# TMC2160.net
KiCad netlist of a schematic drawn in Altium Designer
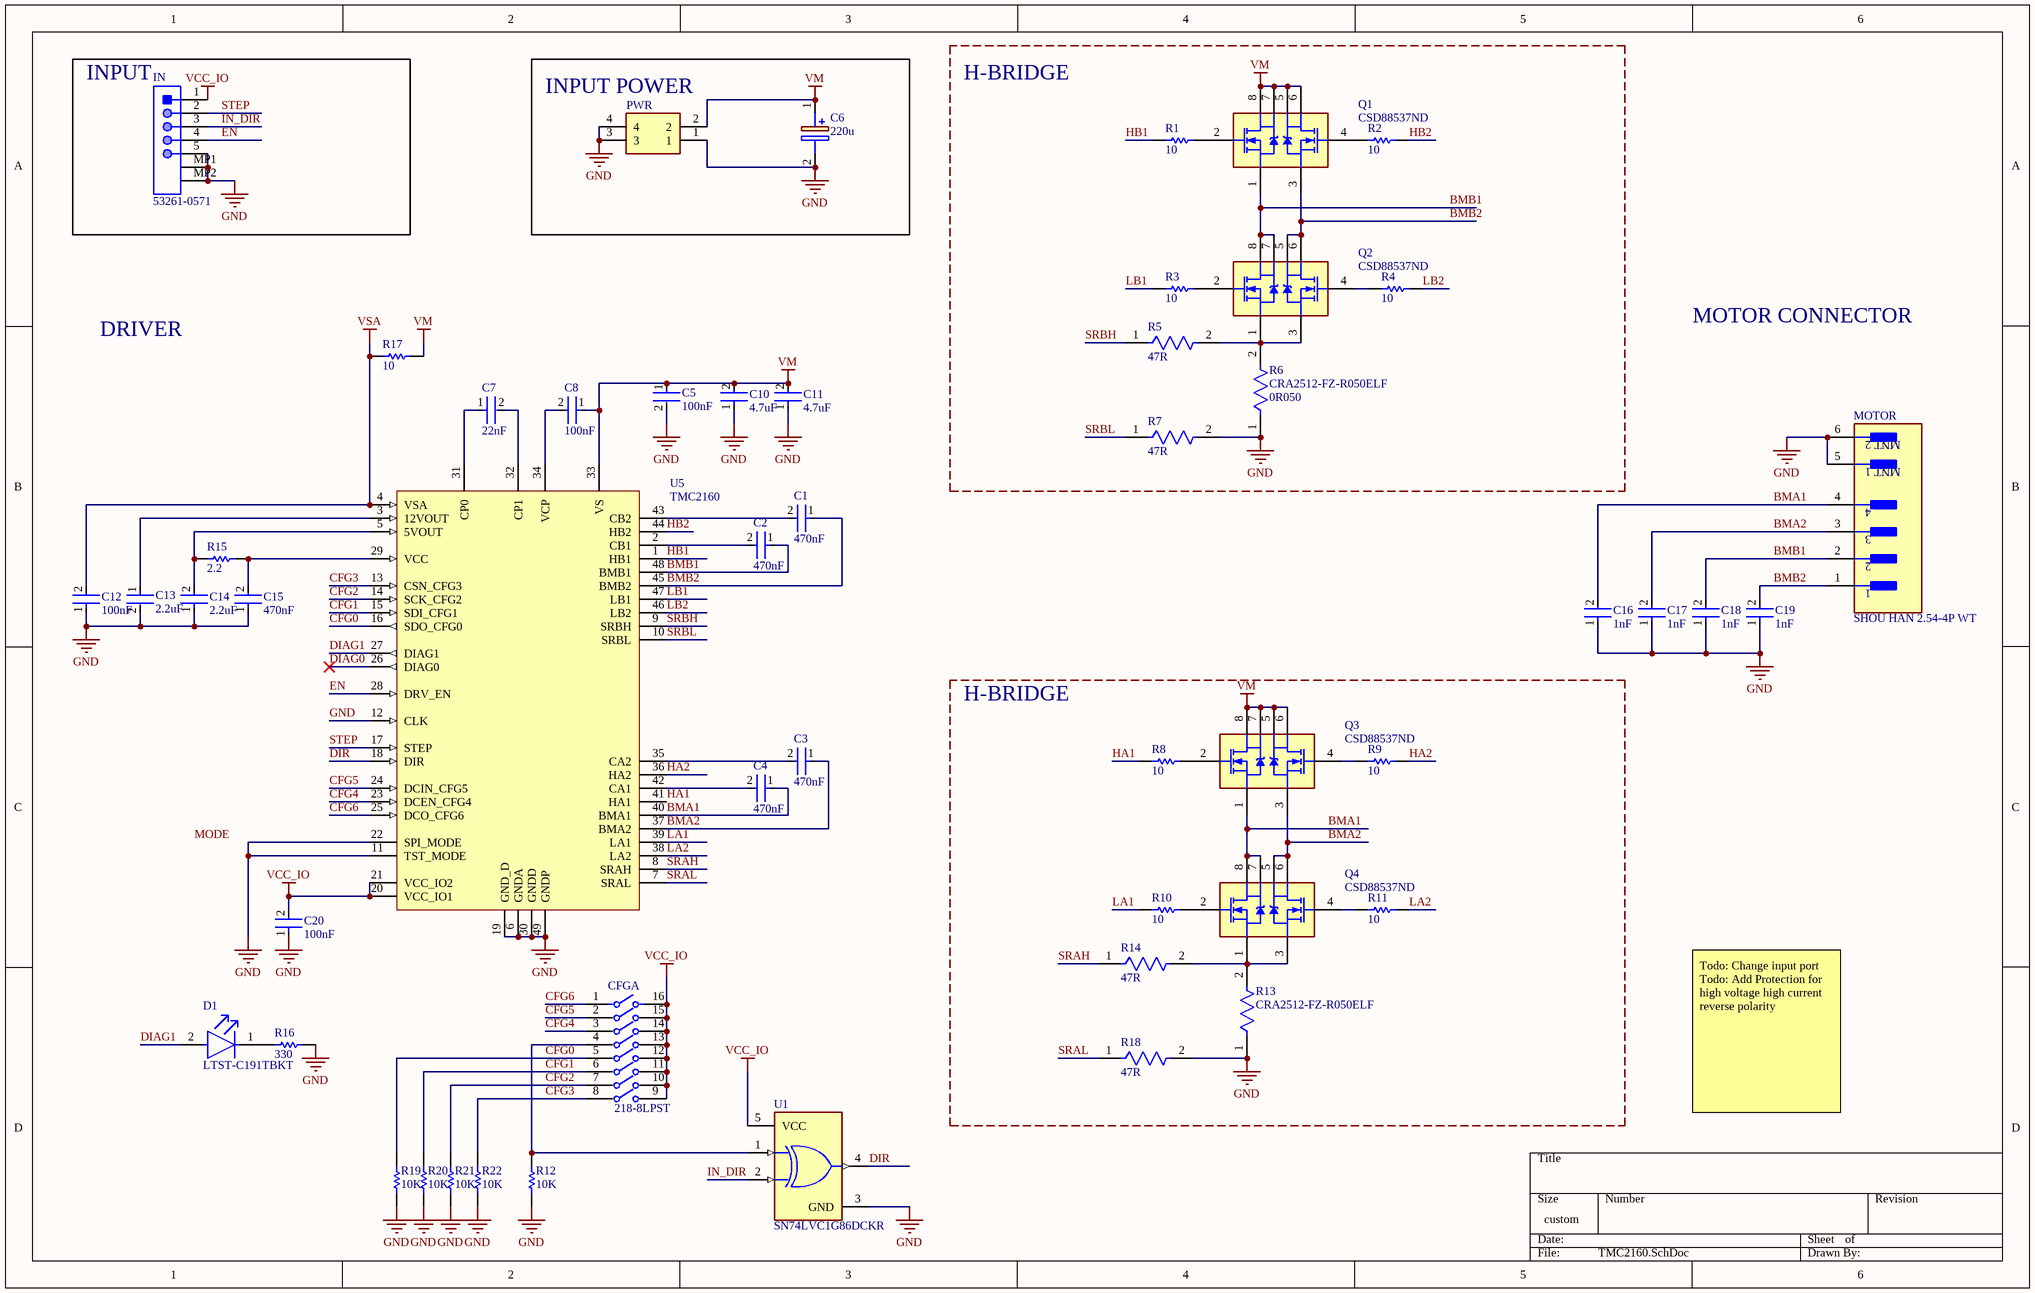
[diagram p0: TMC2160.SchDoc]

(export (version "E")
  (design (tool "Eeschema 10.0.6"))
  (components
    (comp (ref "C1")
      (value "470nF")
      (footprint "FP-C1005-050-0_05-IPC_B")
      (description "Multilayer Ceramic Capacitors 470nF ±10% 35V X5R SMD 0402")
      (fields (field (name "TOLERANCE") "10%") (field (name "Comment") "C1005X5R1V474K050BC"))
      (libsource (lib "Altium Content Vault") (part "b4654b650e69147ec39a6b967a45e02"))
    )
    (comp (ref "C2")
      (value "470nF")
      (footprint "FP-C1005-050-0_05-IPC_B")
      (description "Multilayer Ceramic Capacitors 470nF ±10% 35V X5R SMD 0402")
      (fields (field (name "TOLERANCE") "10%") (field (name "Comment") "C1005X5R1V474K050BC"))
      (libsource (lib "Altium Content Vault") (part "b4654b650e69147ec39a6b967a45e02"))
    )
    (comp (ref "C3")
      (value "470nF")
      (footprint "FP-C1005-050-0_05-IPC_B")
      (description "Multilayer Ceramic Capacitors 470nF ±10% 35V X5R SMD 0402")
      (fields (field (name "TOLERANCE") "10%") (field (name "Comment") "C1005X5R1V474K050BC"))
      (libsource (lib "Altium Content Vault") (part "b4654b650e69147ec39a6b967a45e02"))
    )
    (comp (ref "C4")
      (value "470nF")
      (footprint "FP-C1005-050-0_05-IPC_B")
      (description "Multilayer Ceramic Capacitors 470nF ±10% 35V X5R SMD 0402")
      (fields (field (name "TOLERANCE") "10%") (field (name "Comment") "C1005X5R1V474K050BC"))
      (libsource (lib "Altium Content Vault") (part "b4654b650e69147ec39a6b967a45e02"))
    )
    (comp (ref "C5")
      (value "100nF")
      (footprint "FP-C1005-050-0_05-IPC_C")
      (description "Multilayer Ceramic Capacitors 100nF ±10% 50V X7R SMD 0402")
      (fields (field (name "VOLTAGE") "50V") (field (name "TOLERANCE") "10%"))
      (libsource (lib "Altium Content Vault") (part "b4654b650e69147ec39a6b967a45e02"))
    )
    (comp (ref "C6")
      (value "220u")
      (footprint "SamacSys:CAPAE1030X1050N")
      (description "Capacitor Polarised")
      (fields (field (name "MANUFACTURER_PART_NUMBER") "VZH221M1HTR-1010L"))
      (libsource (lib "SamacSys") (part "VZH221M1HTR-1010L"))
    )
    (comp (ref "C7")
      (value "22nF")
      (footprint "FP-C1005-050-0_05-IPC_C")
      (description "Multilayer Ceramic Capacitors 22nF ±10% 50V X7R SMD 0402")
      (fields (field (name "TOLERANCE") "10%") (field (name "Comment") "C1005X7R1H223K050BB"))
      (libsource (lib "Altium Content Vault") (part "b4654b650e69147ec39a6b967a45e02"))
    )
    (comp (ref "C8")
      (value "100nF")
      (footprint "FP-C1005-050-0_05-IPC_C")
      (description "Multilayer Ceramic Capacitors 100nF ±10% 50V X7R SMD 0402")
      (fields (field (name "VOLTAGE") "50V") (field (name "TOLERANCE") "10%"))
      (libsource (lib "Altium Content Vault") (part "b4654b650e69147ec39a6b967a45e02"))
    )
    (comp (ref "C10")
      (value "4.7uF")
      (footprint "FP-GRM21B-0_15-IPC_B")
      (description "Chip Multilayer Ceramic Capacitors for General Purpose, 0805, 4.7uF, X5R, 15%, 10%, 50V")
      (fields (field (name "TOLERANCE") "10%") (field (name "Comment") "GRM21BR61H475KE51L"))
      (libsource (lib "Altium Content Vault") (part "b4654b650e69147ec39a6b967a45e02"))
    )
    (comp (ref "C11")
      (value "4.7uF")
      (footprint "FP-GRM21B-0_15-IPC_B")
      (description "Chip Multilayer Ceramic Capacitors for General Purpose, 0805, 4.7uF, X5R, 15%, 10%, 50V")
      (fields (field (name "TOLERANCE") "10%") (field (name "Comment") "GRM21BR61H475KE51L"))
      (libsource (lib "Altium Content Vault") (part "b4654b650e69147ec39a6b967a45e02"))
    )
    (comp (ref "C12")
      (value "100nF")
      (footprint "FP-C1005-050-0_05-IPC_C")
      (description "Multilayer Ceramic Capacitors 100nF ±10% 50V X7R SMD 0402")
      (fields (field (name "VOLTAGE") "50V") (field (name "TOLERANCE") "10%"))
      (libsource (lib "Altium Content Vault") (part "b4654b650e69147ec39a6b967a45e02"))
    )
    (comp (ref "C13")
      (value "2.2uF")
      (footprint "FP-C1005-050-0_15-IPC_C")
      (description "CAP CER 2.2UF 35V X5R 0402")
      (fields (field (name "TOLERANCE") "10%") (field (name "Comment") "C1005X5R1V225K050BC"))
      (libsource (lib "Altium Content Vault") (part "11868f565c42a9108669ba33697ecf6"))
    )
    (comp (ref "C14")
      (value "2.2uF")
      (footprint "FP-C1005-050-0_15-IPC_A")
      (description "CAP CER 2.2UF 35V X5R 0402")
      (fields (field (name "TOLERANCE") "10%") (field (name "Comment") "C1005X5R1V225K050BC"))
      (libsource (lib "Altium Content Vault") (part "11868f565c42a9108669ba33697ecf6"))
    )
    (comp (ref "C15")
      (value "470nF")
      (footprint "FP-C1005-050-0_05-IPC_B")
      (description "Multilayer Ceramic Capacitors 470nF ±10% 35V X5R SMD 0402")
      (fields (field (name "TOLERANCE") "10%") (field (name "Comment") "C1005X5R1V474K050BC"))
      (libsource (lib "Altium Content Vault") (part "b4654b650e69147ec39a6b967a45e02"))
    )
    (comp (ref "C16")
      (value "1nF")
      (footprint "FP-C1005-050-0_05-IPC_A")
      (description "Multilayer Ceramic Capacitors 1nF ±10% 50V X7R SMD 0402")
      (fields (field (name "TOLERANCE") "10%") (field (name "VOLTAGE") "50V"))
      (libsource (lib "Altium Content Vault") (part "b4654b650e69147ec39a6b967a45e02"))
    )
    (comp (ref "C17")
      (value "1nF")
      (footprint "FP-C1005-050-0_05-IPC_A")
      (description "Multilayer Ceramic Capacitors 1nF ±10% 50V X7R SMD 0402")
      (fields (field (name "TOLERANCE") "10%") (field (name "VOLTAGE") "50V"))
      (libsource (lib "Altium Content Vault") (part "b4654b650e69147ec39a6b967a45e02"))
    )
    (comp (ref "C18")
      (value "1nF")
      (footprint "FP-C1005-050-0_05-IPC_A")
      (description "Multilayer Ceramic Capacitors 1nF ±10% 50V X7R SMD 0402")
      (fields (field (name "TOLERANCE") "10%") (field (name "VOLTAGE") "50V"))
      (libsource (lib "Altium Content Vault") (part "b4654b650e69147ec39a6b967a45e02"))
    )
    (comp (ref "C19")
      (value "1nF")
      (footprint "FP-C1005-050-0_05-IPC_A")
      (description "Multilayer Ceramic Capacitors 1nF ±10% 50V X7R SMD 0402")
      (fields (field (name "TOLERANCE") "10%") (field (name "VOLTAGE") "50V"))
      (libsource (lib "Altium Content Vault") (part "b4654b650e69147ec39a6b967a45e02"))
    )
    (comp (ref "C20")
      (value "100nF")
      (footprint "FP-C1005-050-0_05-IPC_C")
      (description "Multilayer Ceramic Capacitors 100nF ±10% 50V X7R SMD 0402")
      (fields (field (name "VOLTAGE") "50V") (field (name "TOLERANCE") "10%"))
      (libsource (lib "Altium Content Vault") (part "b4654b650e69147ec39a6b967a45e02"))
    )
    (comp (ref "CFG")
      (value "218-8LPST")
      (footprint "FP-218-8LPST-MFG")
      (description "SWITCH SLIDE DIP SPST 25MA 24V")
      (libsource (lib "Altium Content Vault") (part "c442af63ff53b934e43635f80d8690e"))
    )
    (comp (ref "D1")
      (value "LTST-C191TBKT")
      (footprint "FP-LTST-C191TBKT-MFG")
      (description "LED BLUE CLEAR CHIP SMD")
      (libsource (lib "Altium Content Vault") (part "8706943c75ba83719d021d2fdc84c58"))
    )
    (comp (ref "IN")
      (value "53261-0571")
      (footprint "MOLX-52361-0571-5_V")
      (description "Male Header, Pitch 1.25 mm, 1 x 5 Position, Height 3.4 mm, RoHS, Tape and Reel")
      (fields (field (name "MANUFACTURER") "Molex"))
      (libsource (lib "Altium Content Vault") (part "CN-1P-2M-R5"))
    )
    (comp (ref "MOTOR")
      (value "SHOU HAN 2.54-4P WT")
      (footprint "A2501WF-04A")
      (description "CONN HEADER SMD R/A 4POS 2.5MM")
      (libsource (lib "ParsaLibrary") (part "a9f55b2ccc20dccd0fcbea9c396e26a"))
    )
    (comp (ref "PWR")
      (value "SHOU HAN 2.54-2P WT")
      (footprint "A2501WF-02A")
      (description "Connector")
      (fields
        (field (name "MANUFACTURER_PART_NUMBER") "1778764")
        (field (name "MOUSER PART NUMBER") "651-1778764")
      )
      (libsource (lib "*") (part "1778764"))
    )
    (comp (ref "Q1")
      (value "CSD88537ND")
      (footprint "SamacSys:SOIC127P600X175-8N")
      (description "MOSFET (N-Channel)")
      (fields (field (name "MOUSER PART NUMBER") "595-CSD88537ND"))
      (libsource (lib "SamacSys") (part "CSD88537ND"))
    )
    (comp (ref "Q2")
      (value "CSD88537ND")
      (footprint "SamacSys:SOIC127P600X175-8N")
      (description "MOSFET (N-Channel)")
      (fields (field (name "MOUSER PART NUMBER") "595-CSD88537ND"))
      (libsource (lib "SamacSys") (part "CSD88537ND"))
    )
    (comp (ref "Q3")
      (value "CSD88537ND")
      (footprint "SamacSys:SOIC127P600X175-8N")
      (description "MOSFET (N-Channel)")
      (fields (field (name "MOUSER PART NUMBER") "595-CSD88537ND"))
      (libsource (lib "SamacSys") (part "CSD88537ND"))
    )
    (comp (ref "Q4")
      (value "CSD88537ND")
      (footprint "SamacSys:SOIC127P600X175-8N")
      (description "MOSFET (N-Channel)")
      (fields (field (name "MOUSER PART NUMBER") "595-CSD88537ND"))
      (libsource (lib "SamacSys") (part "CSD88537ND"))
    )
    (comp (ref "R1")
      (value "10")
      (footprint "RESC1005X40X25ML05T10")
      (fields
        (field (name "PART NUMBER") "RC0402FR-07100RL")
        (field (name "MANUFACTURER") "Yageo / Phycomp")
        (field (name "Comment") "RC0402FR-0710RL")
      )
      (libsource (lib "Altium Content Vault") (part "RES"))
    )
    (comp (ref "R2")
      (value "10")
      (footprint "RESC1005X40X25ML05T10")
      (fields
        (field (name "PART NUMBER") "RC0402FR-07100RL")
        (field (name "MANUFACTURER") "Yageo / Phycomp")
        (field (name "Comment") "RC0402FR-0710RL")
      )
      (libsource (lib "Altium Content Vault") (part "RES"))
    )
    (comp (ref "R3")
      (value "10")
      (footprint "RESC1005X40X25ML05T10")
      (fields
        (field (name "PART NUMBER") "RC0402FR-07100RL")
        (field (name "MANUFACTURER") "Yageo / Phycomp")
        (field (name "Comment") "RC0402FR-0710RL")
      )
      (libsource (lib "Altium Content Vault") (part "RES"))
    )
    (comp (ref "R4")
      (value "10")
      (footprint "RESC1005X40X25ML05T10")
      (fields
        (field (name "PART NUMBER") "RC0402FR-07100RL")
        (field (name "MANUFACTURER") "Yageo / Phycomp")
        (field (name "Comment") "RC0402FR-0710RL")
      )
      (libsource (lib "Altium Content Vault") (part "RES"))
    )
    (comp (ref "R5")
      (value "47R")
      (footprint "FP-ERJ2RK-IPC_C")
      (description "RES SMD 47 OHM 1% 1/10W 0402")
      (fields (field (name "TOLERANCE") "1%") (field (name "Comment") "ERJ-2RKF47R0X"))
      (libsource (lib "Altium Content Vault") (part "1029c3af85768c4190bb7ad29bc67b5"))
    )
    (comp (ref "R6")
      (value "CRA2512-FZ-R050ELF")
      (footprint "FP-CRA2512-IPC_A")
      (description "RES 0.05 OHM 1% 3W 2512")
      (fields (field (name "ALTIUM_VALUE") "0R050"))
      (libsource (lib "Altium Content Vault") (part "1029c3af85768c4190bb7ad29bc67b5"))
    )
    (comp (ref "R7")
      (value "47R")
      (footprint "FP-ERJ2RK-IPC_C")
      (description "RES SMD 47 OHM 1% 1/10W 0402")
      (fields (field (name "TOLERANCE") "1%") (field (name "Comment") "ERJ-2RKF47R0X"))
      (libsource (lib "Altium Content Vault") (part "1029c3af85768c4190bb7ad29bc67b5"))
    )
    (comp (ref "R8")
      (value "10")
      (footprint "RESC1005X40X25ML05T10")
      (fields
        (field (name "PART NUMBER") "RC0402FR-07100RL")
        (field (name "MANUFACTURER") "Yageo / Phycomp")
        (field (name "Comment") "RC0402FR-0710RL")
      )
      (libsource (lib "Altium Content Vault") (part "RES"))
    )
    (comp (ref "R9")
      (value "10")
      (footprint "RESC1005X40X25ML05T10")
      (fields
        (field (name "PART NUMBER") "RC0402FR-07100RL")
        (field (name "MANUFACTURER") "Yageo / Phycomp")
        (field (name "Comment") "RC0402FR-0710RL")
      )
      (libsource (lib "Altium Content Vault") (part "RES"))
    )
    (comp (ref "R10")
      (value "10")
      (footprint "RESC1005X40X25ML05T10")
      (fields
        (field (name "PART NUMBER") "RC0402FR-07100RL")
        (field (name "MANUFACTURER") "Yageo / Phycomp")
        (field (name "Comment") "RC0402FR-0710RL")
      )
      (libsource (lib "Altium Content Vault") (part "RES"))
    )
    (comp (ref "R11")
      (value "10")
      (footprint "RESC1005X40X25ML05T10")
      (fields
        (field (name "PART NUMBER") "RC0402FR-07100RL")
        (field (name "MANUFACTURER") "Yageo / Phycomp")
        (field (name "Comment") "RC0402FR-0710RL")
      )
      (libsource (lib "Altium Content Vault") (part "RES"))
    )
    (comp (ref "R12")
      (value "10K")
      (footprint "RESC1005X40X25LL05T10")
      (fields (field (name "PART NUMBER") "RC0402FR-0710KL") (field (name "MANUFACTURER") "Yageo / Phycomp"))
      (libsource (lib "Altium Content Vault") (part "RES"))
    )
    (comp (ref "R13")
      (value "CRA2512-FZ-R050ELF")
      (footprint "FP-CRA2512-IPC_A")
      (description "RES 0.05 OHM 1% 3W 2512")
      (libsource (lib "Altium Content Vault") (part "1029c3af85768c4190bb7ad29bc67b5"))
    )
    (comp (ref "R14")
      (value "47R")
      (footprint "FP-ERJ2RK-IPC_C")
      (description "RES SMD 47 OHM 1% 1/10W 0402")
      (fields (field (name "TOLERANCE") "1%") (field (name "Comment") "ERJ-2RKF47R0X"))
      (libsource (lib "Altium Content Vault") (part "1029c3af85768c4190bb7ad29bc67b5"))
    )
    (comp (ref "R15")
      (value "ERJ-2GEJ2R2X")
      (footprint "RESC1005X40X25ML05T05")
      (fields (field (name "MANUFACTURER") "Panasonic") (field (name "RESISTANCE") "2.2"))
      (libsource (lib "Altium Content Vault") (part "RES"))
    )
    (comp (ref "R16")
      (value "330")
      (footprint "RESC1005X40X25LL05T10")
      (fields (field (name "PART NUMBER") "RC0402FR-07330RL") (field (name "MANUFACTURER") "Yageo / Phycomp"))
      (libsource (lib "Altium Content Vault") (part "RES"))
    )
    (comp (ref "R17")
      (value "10")
      (footprint "RESC1005X40X25ML05T10")
      (fields
        (field (name "PART NUMBER") "RC0402FR-07100RL")
        (field (name "MANUFACTURER") "Yageo / Phycomp")
        (field (name "Comment") "RC0402FR-0710RL")
      )
      (libsource (lib "Altium Content Vault") (part "RES"))
    )
    (comp (ref "R18")
      (value "47R")
      (footprint "FP-ERJ2RK-IPC_C")
      (description "RES SMD 47 OHM 1% 1/10W 0402")
      (fields (field (name "TOLERANCE") "1%") (field (name "Comment") "ERJ-2RKF47R0X"))
      (libsource (lib "Altium Content Vault") (part "1029c3af85768c4190bb7ad29bc67b5"))
    )
    (comp (ref "R19")
      (value "10K")
      (footprint "RESC1005X40X25LL05T10")
      (fields (field (name "PART NUMBER") "RC0402FR-0710KL") (field (name "MANUFACTURER") "Yageo / Phycomp"))
      (libsource (lib "Altium Content Vault") (part "RES"))
    )
    (comp (ref "R20")
      (value "10K")
      (footprint "RESC1005X40X25LL05T10")
      (fields (field (name "PART NUMBER") "RC0402FR-0710KL") (field (name "MANUFACTURER") "Yageo / Phycomp"))
      (libsource (lib "Altium Content Vault") (part "RES"))
    )
    (comp (ref "R21")
      (value "10K")
      (footprint "RESC1005X40X25LL05T10")
      (fields (field (name "PART NUMBER") "RC0402FR-0710KL") (field (name "MANUFACTURER") "Yageo / Phycomp"))
      (libsource (lib "Altium Content Vault") (part "RES"))
    )
    (comp (ref "R22")
      (value "10K")
      (footprint "RESC1005X40X25LL05T10")
      (fields (field (name "PART NUMBER") "RC0402FR-0710KL") (field (name "MANUFACTURER") "Yageo / Phycomp"))
      (libsource (lib "Altium Content Vault") (part "RES"))
    )
    (comp (ref "U1")
      (value "SN74LVC1G86DCKR")
      (footprint "FP-DCK0005A-MFG")
      (description "IC GATE XOR 1CH 2-INP SC70-5")
      (fields
        (field (name "MANUFACTURER") "Texas Instruments")
        (field (name "OCTOPART") "https://octopart.com/sn74lvc1g86dckr-texas+instruments-465565")
      )
      (libsource (lib "Altium Content Vault") (part "16ef8527b9de762b4e4b42e13c10760"))
    )
    (comp (ref "U5") (value "TMC2160") (footprint "TSQFP-48") (libsource (lib "Schlib2") (part "TMC2160")))
  )
  (nets
    (net (code "1") (name "/BMA1") (class "Default")
      (node (ref "C16") (pin "2") (pinfunction "2_2") (pintype "passive"))
      (node (ref "C4") (pin "1") (pinfunction "1_1") (pintype "passive"))
      (node (ref "MOTOR") (pin "4") (pinfunction "4_4") (pintype "passive"))
      (node (ref "Q3") (pin "1") (pinfunction "S1_1") (pintype "passive"))
      (node (ref "Q4") (pin "7") (pinfunction "D1_1_7") (pintype "passive"))
      (node (ref "Q4") (pin "8") (pinfunction "D1_2_8") (pintype "passive"))
      (node (ref "U5") (pin "40") (pinfunction "BMA1_40") (pintype "passive"))
    )
    (net (code "2") (name "/BMA2") (class "Default")
      (node (ref "C17") (pin "2") (pinfunction "2_2") (pintype "passive"))
      (node (ref "C3") (pin "1") (pinfunction "1_1") (pintype "passive"))
      (node (ref "MOTOR") (pin "3") (pinfunction "3_3") (pintype "passive"))
      (node (ref "Q3") (pin "3") (pinfunction "S2_3") (pintype "passive"))
      (node (ref "Q4") (pin "5") (pinfunction "D2_1_5") (pintype "passive"))
      (node (ref "Q4") (pin "6") (pinfunction "D2_2_6") (pintype "passive"))
      (node (ref "U5") (pin "37") (pinfunction "BMA2_37") (pintype "passive"))
    )
    (net (code "3") (name "/BMB1") (class "Default")
      (node (ref "C18") (pin "2") (pinfunction "2_2") (pintype "passive"))
      (node (ref "C2") (pin "1") (pinfunction "1_1") (pintype "passive"))
      (node (ref "MOTOR") (pin "2") (pinfunction "2_2") (pintype "passive"))
      (node (ref "Q1") (pin "1") (pinfunction "S1_1") (pintype "passive"))
      (node (ref "Q2") (pin "7") (pinfunction "D1_1_7") (pintype "passive"))
      (node (ref "Q2") (pin "8") (pinfunction "D1_2_8") (pintype "passive"))
      (node (ref "U5") (pin "48") (pinfunction "BMB1_48") (pintype "passive"))
    )
    (net (code "4") (name "/BMB2") (class "Default")
      (node (ref "C1") (pin "1") (pinfunction "1_1") (pintype "passive"))
      (node (ref "C19") (pin "2") (pinfunction "2_2") (pintype "passive"))
      (node (ref "MOTOR") (pin "1") (pinfunction "1_1") (pintype "passive"))
      (node (ref "Q1") (pin "3") (pinfunction "S2_3") (pintype "passive"))
      (node (ref "Q2") (pin "5") (pinfunction "D2_1_5") (pintype "passive"))
      (node (ref "Q2") (pin "6") (pinfunction "D2_2_6") (pintype "passive"))
      (node (ref "U5") (pin "45") (pinfunction "BMB2_45") (pintype "passive"))
    )
    (net (code "5") (name "/CFG0") (class "Default")
      (node (ref "CFG") (pin "5") (pinfunction "5_5") (pintype "passive"))
      (node (ref "R19") (pin "2") (pinfunction "2_2") (pintype "passive"))
      (node (ref "U5") (pin "16") (pinfunction "SDO_CFG0_16") (pintype "output"))
    )
    (net (code "6") (name "/CFG1") (class "Default")
      (node (ref "CFG") (pin "6") (pinfunction "6_6") (pintype "passive"))
      (node (ref "R20") (pin "2") (pinfunction "2_2") (pintype "passive"))
      (node (ref "U5") (pin "15") (pinfunction "SDI_CFG1_15") (pintype "input"))
    )
    (net (code "7") (name "/CFG2") (class "Default")
      (node (ref "CFG") (pin "7") (pinfunction "7_7") (pintype "passive"))
      (node (ref "R21") (pin "2") (pinfunction "2_2") (pintype "passive"))
      (node (ref "U5") (pin "14") (pinfunction "SCK_CFG2_14") (pintype "input"))
    )
    (net (code "8") (name "/CFG3") (class "Default")
      (node (ref "CFG") (pin "8") (pinfunction "8_8") (pintype "passive"))
      (node (ref "R22") (pin "2") (pinfunction "2_2") (pintype "passive"))
      (node (ref "U5") (pin "13") (pinfunction "CSN_CFG3_13") (pintype "input"))
    )
    (net (code "9") (name "/CFG4") (class "Default")
      (node (ref "CFG") (pin "3") (pinfunction "3_3") (pintype "passive"))
      (node (ref "U5") (pin "23") (pinfunction "DCEN_CFG4_23") (pintype "input"))
    )
    (net (code "10") (name "/CFG5") (class "Default")
      (node (ref "CFG") (pin "2") (pinfunction "2_2") (pintype "passive"))
      (node (ref "U5") (pin "24") (pinfunction "DCIN_CFG5_24") (pintype "input"))
    )
    (net (code "11") (name "/CFG6") (class "Default")
      (node (ref "CFG") (pin "1") (pinfunction "1_1") (pintype "passive"))
      (node (ref "U5") (pin "25") (pinfunction "DCO_CFG6_25") (pintype "input"))
    )
    (net (code "12") (name "/DIAG0") (class "Default")
      (node (ref "U5") (pin "26") (pinfunction "DIAG0_26") (pintype "output+no_connect"))
    )
    (net (code "13") (name "/DIAG1") (class "Default")
      (node (ref "D1") (pin "2") (pinfunction "A_2") (pintype "passive"))
      (node (ref "U5") (pin "27") (pinfunction "DIAG1_27") (pintype "output"))
    )
    (net (code "14") (name "/DIR") (class "Default")
      (node (ref "U1") (pin "4") (pinfunction "Y_4") (pintype "output"))
      (node (ref "U5") (pin "18") (pinfunction "DIR_18") (pintype "input"))
    )
    (net (code "15") (name "/EN") (class "Default")
      (node (ref "IN") (pin "4") (pinfunction "4_4") (pintype "passive"))
      (node (ref "U5") (pin "28") (pinfunction "DRV_EN_28") (pintype "input"))
    )
    (net (code "16") (name "/HA1") (class "Default")
      (node (ref "R8") (pin "2") (pinfunction "2_2") (pintype "passive"))
      (node (ref "U5") (pin "41") (pinfunction "HA1_41") (pintype "passive"))
    )
    (net (code "17") (name "/HA2") (class "Default")
      (node (ref "R9") (pin "1") (pinfunction "1_1") (pintype "passive"))
      (node (ref "U5") (pin "36") (pinfunction "HA2_36") (pintype "passive"))
    )
    (net (code "18") (name "/HB1") (class "Default")
      (node (ref "R1") (pin "2") (pinfunction "2_2") (pintype "passive"))
      (node (ref "U5") (pin "1") (pinfunction "HB1_1") (pintype "passive"))
    )
    (net (code "19") (name "/HB2") (class "Default")
      (node (ref "R2") (pin "1") (pinfunction "1_1") (pintype "passive"))
      (node (ref "U5") (pin "44") (pinfunction "HB2_44") (pintype "passive"))
    )
    (net (code "20") (name "/IN_DIR") (class "Default")
      (node (ref "IN") (pin "3") (pinfunction "3_3") (pintype "passive"))
      (node (ref "U1") (pin "2") (pinfunction "B_2") (pintype "input"))
    )
    (net (code "21") (name "/LA1") (class "Default")
      (node (ref "R10") (pin "2") (pinfunction "2_2") (pintype "passive"))
      (node (ref "U5") (pin "39") (pinfunction "LA1_39") (pintype "passive"))
    )
    (net (code "22") (name "/LA2") (class "Default")
      (node (ref "R11") (pin "1") (pinfunction "1_1") (pintype "passive"))
      (node (ref "U5") (pin "38") (pinfunction "LA2_38") (pintype "passive"))
    )
    (net (code "23") (name "/LB1") (class "Default")
      (node (ref "R3") (pin "2") (pinfunction "2_2") (pintype "passive"))
      (node (ref "U5") (pin "47") (pinfunction "LB1_47") (pintype "passive"))
    )
    (net (code "24") (name "/LB2") (class "Default")
      (node (ref "R4") (pin "1") (pinfunction "1_1") (pintype "passive"))
      (node (ref "U5") (pin "46") (pinfunction "LB2_46") (pintype "passive"))
    )
    (net (code "26") (name "/SRAH") (class "Default")
      (node (ref "R14") (pin "1") (pinfunction "1_1") (pintype "passive"))
      (node (ref "U5") (pin "8") (pinfunction "SRAH_8") (pintype "passive"))
    )
    (net (code "27") (name "/SRAL") (class "Default")
      (node (ref "R18") (pin "1") (pinfunction "1_1") (pintype "passive"))
      (node (ref "U5") (pin "7") (pinfunction "SRAL_7") (pintype "passive"))
    )
    (net (code "28") (name "/SRBH") (class "Default")
      (node (ref "R5") (pin "1") (pinfunction "1_1") (pintype "passive"))
      (node (ref "U5") (pin "9") (pinfunction "SRBH_9") (pintype "passive"))
    )
    (net (code "29") (name "/SRBL") (class "Default")
      (node (ref "R7") (pin "1") (pinfunction "1_1") (pintype "passive"))
      (node (ref "U5") (pin "10") (pinfunction "SRBL_10") (pintype "passive"))
    )
    (net (code "30") (name "/STEP") (class "Default")
      (node (ref "IN") (pin "2") (pinfunction "2_2") (pintype "passive"))
      (node (ref "U5") (pin "17") (pinfunction "STEP_17") (pintype "input"))
    )
    (net (code "31") (name "GND") (class "Default")
      (node (ref "C10") (pin "1") (pinfunction "1_1") (pintype "passive"))
      (node (ref "C11") (pin "1") (pinfunction "1_1") (pintype "passive"))
      (node (ref "C12") (pin "1") (pinfunction "1_1") (pintype "passive"))
      (node (ref "C13") (pin "2") (pinfunction "2_2") (pintype "passive"))
      (node (ref "C14") (pin "1") (pinfunction "1_1") (pintype "passive"))
      (node (ref "C15") (pin "1") (pinfunction "1_1") (pintype "passive"))
      (node (ref "C16") (pin "1") (pinfunction "1_1") (pintype "passive"))
      (node (ref "C17") (pin "1") (pinfunction "1_1") (pintype "passive"))
      (node (ref "C18") (pin "1") (pinfunction "1_1") (pintype "passive"))
      (node (ref "C19") (pin "1") (pinfunction "1_1") (pintype "passive"))
      (node (ref "C20") (pin "1") (pinfunction "1_1") (pintype "passive"))
      (node (ref "C5") (pin "2") (pinfunction "2_2") (pintype "passive"))
      (node (ref "C6") (pin "2") (pinfunction "-_2") (pintype "passive"))
      (node (ref "IN") (pin "5") (pinfunction "5_5") (pintype "passive"))
      (node (ref "IN") (pin "MP1") (pinfunction "MP1_MP1") (pintype "passive"))
      (node (ref "IN") (pin "MP2") (pinfunction "MP2_MP2") (pintype "passive"))
      (node (ref "MOTOR") (pin "5") (pinfunction "MNT_1_5") (pintype "passive"))
      (node (ref "MOTOR") (pin "6") (pinfunction "MNT_2_6") (pintype "passive"))
      (node (ref "PWR") (pin "1") (pinfunction "1_1") (pintype "passive"))
      (node (ref "PWR") (pin "3") (pinfunction "3_3") (pintype "passive"))
      (node (ref "PWR") (pin "4") (pinfunction "4_4") (pintype "passive"))
      (node (ref "R12") (pin "1") (pinfunction "1_1") (pintype "passive"))
      (node (ref "R13") (pin "1") (pinfunction "1_1") (pintype "passive"))
      (node (ref "R16") (pin "1") (pinfunction "1_1") (pintype "passive"))
      (node (ref "R18") (pin "2") (pinfunction "2_2") (pintype "passive"))
      (node (ref "R19") (pin "1") (pinfunction "1_1") (pintype "passive"))
      (node (ref "R20") (pin "1") (pinfunction "1_1") (pintype "passive"))
      (node (ref "R21") (pin "1") (pinfunction "1_1") (pintype "passive"))
      (node (ref "R22") (pin "1") (pinfunction "1_1") (pintype "passive"))
      (node (ref "R6") (pin "1") (pinfunction "1_1") (pintype "passive"))
      (node (ref "R7") (pin "2") (pinfunction "2_2") (pintype "passive"))
      (node (ref "U1") (pin "3") (pinfunction "GND_3") (pintype "power_in"))
      (node (ref "U5") (pin "11") (pinfunction "TST_MODE_11") (pintype "passive"))
      (node (ref "U5") (pin "12") (pinfunction "CLK_12") (pintype "input"))
      (node (ref "U5") (pin "19") (pinfunction "GND_D_19") (pintype "power_in"))
      (node (ref "U5") (pin "22") (pinfunction "SPI_MODE_22") (pintype "passive"))
      (node (ref "U5") (pin "30") (pinfunction "GNDD_30") (pintype "power_in"))
      (node (ref "U5") (pin "49") (pinfunction "GNDP_49") (pintype "power_in"))
      (node (ref "U5") (pin "6") (pinfunction "GNDA_6") (pintype "power_in"))
    )
    (net (code "32") (name "Net-(D1-C)") (class "Default")
      (node (ref "D1") (pin "1") (pinfunction "C_1") (pintype "passive"))
      (node (ref "R16") (pin "2") (pinfunction "2_2") (pintype "passive"))
    )
    (net (code "33") (name "Net-(Q1-G1)") (class "Default")
      (node (ref "Q1") (pin "2") (pinfunction "G1_2") (pintype "passive"))
      (node (ref "R1") (pin "1") (pinfunction "1_1") (pintype "passive"))
    )
    (net (code "34") (name "Net-(Q1-G2)") (class "Default")
      (node (ref "Q1") (pin "4") (pinfunction "G2_4") (pintype "passive"))
      (node (ref "R2") (pin "2") (pinfunction "2_2") (pintype "passive"))
    )
    (net (code "35") (name "Net-(Q2-G1)") (class "Default")
      (node (ref "Q2") (pin "2") (pinfunction "G1_2") (pintype "passive"))
      (node (ref "R3") (pin "1") (pinfunction "1_1") (pintype "passive"))
    )
    (net (code "36") (name "Net-(Q2-G2)") (class "Default")
      (node (ref "Q2") (pin "4") (pinfunction "G2_4") (pintype "passive"))
      (node (ref "R4") (pin "2") (pinfunction "2_2") (pintype "passive"))
    )
    (net (code "37") (name "Net-(Q2-S1)") (class "Default")
      (node (ref "Q2") (pin "1") (pinfunction "S1_1") (pintype "passive"))
      (node (ref "Q2") (pin "3") (pinfunction "S2_3") (pintype "passive"))
      (node (ref "R5") (pin "2") (pinfunction "2_2") (pintype "passive"))
      (node (ref "R6") (pin "2") (pinfunction "2_2") (pintype "passive"))
    )
    (net (code "38") (name "Net-(Q3-G1)") (class "Default")
      (node (ref "Q3") (pin "2") (pinfunction "G1_2") (pintype "passive"))
      (node (ref "R8") (pin "1") (pinfunction "1_1") (pintype "passive"))
    )
    (net (code "39") (name "Net-(Q3-G2)") (class "Default")
      (node (ref "Q3") (pin "4") (pinfunction "G2_4") (pintype "passive"))
      (node (ref "R9") (pin "2") (pinfunction "2_2") (pintype "passive"))
    )
    (net (code "40") (name "Net-(Q4-G1)") (class "Default")
      (node (ref "Q4") (pin "2") (pinfunction "G1_2") (pintype "passive"))
      (node (ref "R10") (pin "1") (pinfunction "1_1") (pintype "passive"))
    )
    (net (code "41") (name "Net-(Q4-G2)") (class "Default")
      (node (ref "Q4") (pin "4") (pinfunction "G2_4") (pintype "passive"))
      (node (ref "R11") (pin "2") (pinfunction "2_2") (pintype "passive"))
    )
    (net (code "42") (name "Net-(Q4-S1)") (class "Default")
      (node (ref "Q4") (pin "1") (pinfunction "S1_1") (pintype "passive"))
      (node (ref "Q4") (pin "3") (pinfunction "S2_3") (pintype "passive"))
      (node (ref "R13") (pin "2") (pinfunction "2_2") (pintype "passive"))
      (node (ref "R14") (pin "2") (pinfunction "2_2") (pintype "passive"))
    )
    (net (code "43") (name "Net-(U1-A)") (class "Default")
      (node (ref "CFG") (pin "4") (pinfunction "4_4") (pintype "passive"))
      (node (ref "R12") (pin "2") (pinfunction "2_2") (pintype "passive"))
      (node (ref "U1") (pin "1") (pinfunction "A_1") (pintype "input"))
    )
    (net (code "44") (name "Net-(U5-5VOUT)") (class "Default")
      (node (ref "C14") (pin "2") (pinfunction "2_2") (pintype "passive"))
      (node (ref "R15") (pin "2") (pinfunction "2_2") (pintype "passive"))
      (node (ref "U5") (pin "5") (pinfunction "5VOUT_5") (pintype "input"))
    )
    (net (code "45") (name "Net-(U5-12VOUT)") (class "Default")
      (node (ref "C13") (pin "1") (pinfunction "1_1") (pintype "passive"))
      (node (ref "U5") (pin "3") (pinfunction "12VOUT_3") (pintype "input"))
    )
    (net (code "46") (name "Net-(U5-CA1)") (class "Default")
      (node (ref "C4") (pin "2") (pinfunction "2_2") (pintype "passive"))
      (node (ref "U5") (pin "42") (pinfunction "CA1_42") (pintype "passive"))
    )
    (net (code "47") (name "Net-(U5-CA2)") (class "Default")
      (node (ref "C3") (pin "2") (pinfunction "2_2") (pintype "passive"))
      (node (ref "U5") (pin "35") (pinfunction "CA2_35") (pintype "passive"))
    )
    (net (code "48") (name "Net-(U5-CB1)") (class "Default")
      (node (ref "C2") (pin "2") (pinfunction "2_2") (pintype "passive"))
      (node (ref "U5") (pin "2") (pinfunction "CB1_2") (pintype "passive"))
    )
    (net (code "49") (name "Net-(U5-CB2)") (class "Default")
      (node (ref "C1") (pin "2") (pinfunction "2_2") (pintype "passive"))
      (node (ref "U5") (pin "43") (pinfunction "CB2_43") (pintype "passive"))
    )
    (net (code "50") (name "Net-(U5-CP0)") (class "Default")
      (node (ref "C7") (pin "1") (pinfunction "1_1") (pintype "passive"))
      (node (ref "U5") (pin "31") (pinfunction "CP0_31") (pintype "power_in"))
    )
    (net (code "51") (name "Net-(U5-CP1)") (class "Default")
      (node (ref "C7") (pin "2") (pinfunction "2_2") (pintype "passive"))
      (node (ref "U5") (pin "32") (pinfunction "CP1_32") (pintype "power_in"))
    )
    (net (code "52") (name "Net-(U5-VCC)") (class "Default")
      (node (ref "C15") (pin "2") (pinfunction "2_2") (pintype "passive"))
      (node (ref "R15") (pin "1") (pinfunction "1_1") (pintype "passive"))
      (node (ref "U5") (pin "29") (pinfunction "VCC_29") (pintype "input"))
    )
    (net (code "53") (name "Net-(U5-VCP)") (class "Default")
      (node (ref "C8") (pin "2") (pinfunction "2_2") (pintype "passive"))
      (node (ref "U5") (pin "34") (pinfunction "VCP_34") (pintype "power_in"))
    )
    (net (code "54") (name "VCC_IO") (class "Default")
      (node (ref "C20") (pin "2") (pinfunction "2_2") (pintype "passive"))
      (node (ref "CFG") (pin "10") (pinfunction "10_10") (pintype "passive"))
      (node (ref "CFG") (pin "11") (pinfunction "11_11") (pintype "passive"))
      (node (ref "CFG") (pin "12") (pinfunction "12_12") (pintype "passive"))
      (node (ref "CFG") (pin "13") (pinfunction "13_13") (pintype "passive"))
      (node (ref "CFG") (pin "14") (pinfunction "14_14") (pintype "passive"))
      (node (ref "CFG") (pin "15") (pinfunction "15_15") (pintype "passive"))
      (node (ref "CFG") (pin "16") (pinfunction "16_16") (pintype "passive"))
      (node (ref "CFG") (pin "9") (pinfunction "9_9") (pintype "passive"))
      (node (ref "IN") (pin "1") (pinfunction "1_1") (pintype "passive"))
      (node (ref "U1") (pin "5") (pinfunction "VCC_5") (pintype "power_in"))
      (node (ref "U5") (pin "20") (pinfunction "VCC_IO1_20") (pintype "power_in"))
      (node (ref "U5") (pin "21") (pinfunction "VCC_IO2_21") (pintype "power_in"))
    )
    (net (code "55") (name "VM") (class "Default")
      (node (ref "C10") (pin "2") (pinfunction "2_2") (pintype "passive"))
      (node (ref "C11") (pin "2") (pinfunction "2_2") (pintype "passive"))
      (node (ref "C5") (pin "1") (pinfunction "1_1") (pintype "passive"))
      (node (ref "C6") (pin "1") (pinfunction "+_1") (pintype "passive"))
      (node (ref "C8") (pin "1") (pinfunction "1_1") (pintype "passive"))
      (node (ref "PWR") (pin "2") (pinfunction "2_2") (pintype "passive"))
      (node (ref "Q1") (pin "5") (pinfunction "D2_1_5") (pintype "passive"))
      (node (ref "Q1") (pin "6") (pinfunction "D2_2_6") (pintype "passive"))
      (node (ref "Q1") (pin "7") (pinfunction "D1_1_7") (pintype "passive"))
      (node (ref "Q1") (pin "8") (pinfunction "D1_2_8") (pintype "passive"))
      (node (ref "Q3") (pin "5") (pinfunction "D2_1_5") (pintype "passive"))
      (node (ref "Q3") (pin "6") (pinfunction "D2_2_6") (pintype "passive"))
      (node (ref "Q3") (pin "7") (pinfunction "D1_1_7") (pintype "passive"))
      (node (ref "Q3") (pin "8") (pinfunction "D1_2_8") (pintype "passive"))
      (node (ref "R17") (pin "1") (pinfunction "1_1") (pintype "passive"))
      (node (ref "U5") (pin "33") (pinfunction "VS_33") (pintype "power_in"))
    )
    (net (code "56") (name "VSA") (class "Default")
      (node (ref "C12") (pin "2") (pinfunction "2_2") (pintype "passive"))
      (node (ref "R17") (pin "2") (pinfunction "2_2") (pintype "passive"))
      (node (ref "U5") (pin "4") (pinfunction "VSA_4") (pintype "input"))
    )
  )
)
